# untitled.net
KiCad netlist of a schematic drawn in EAGLE
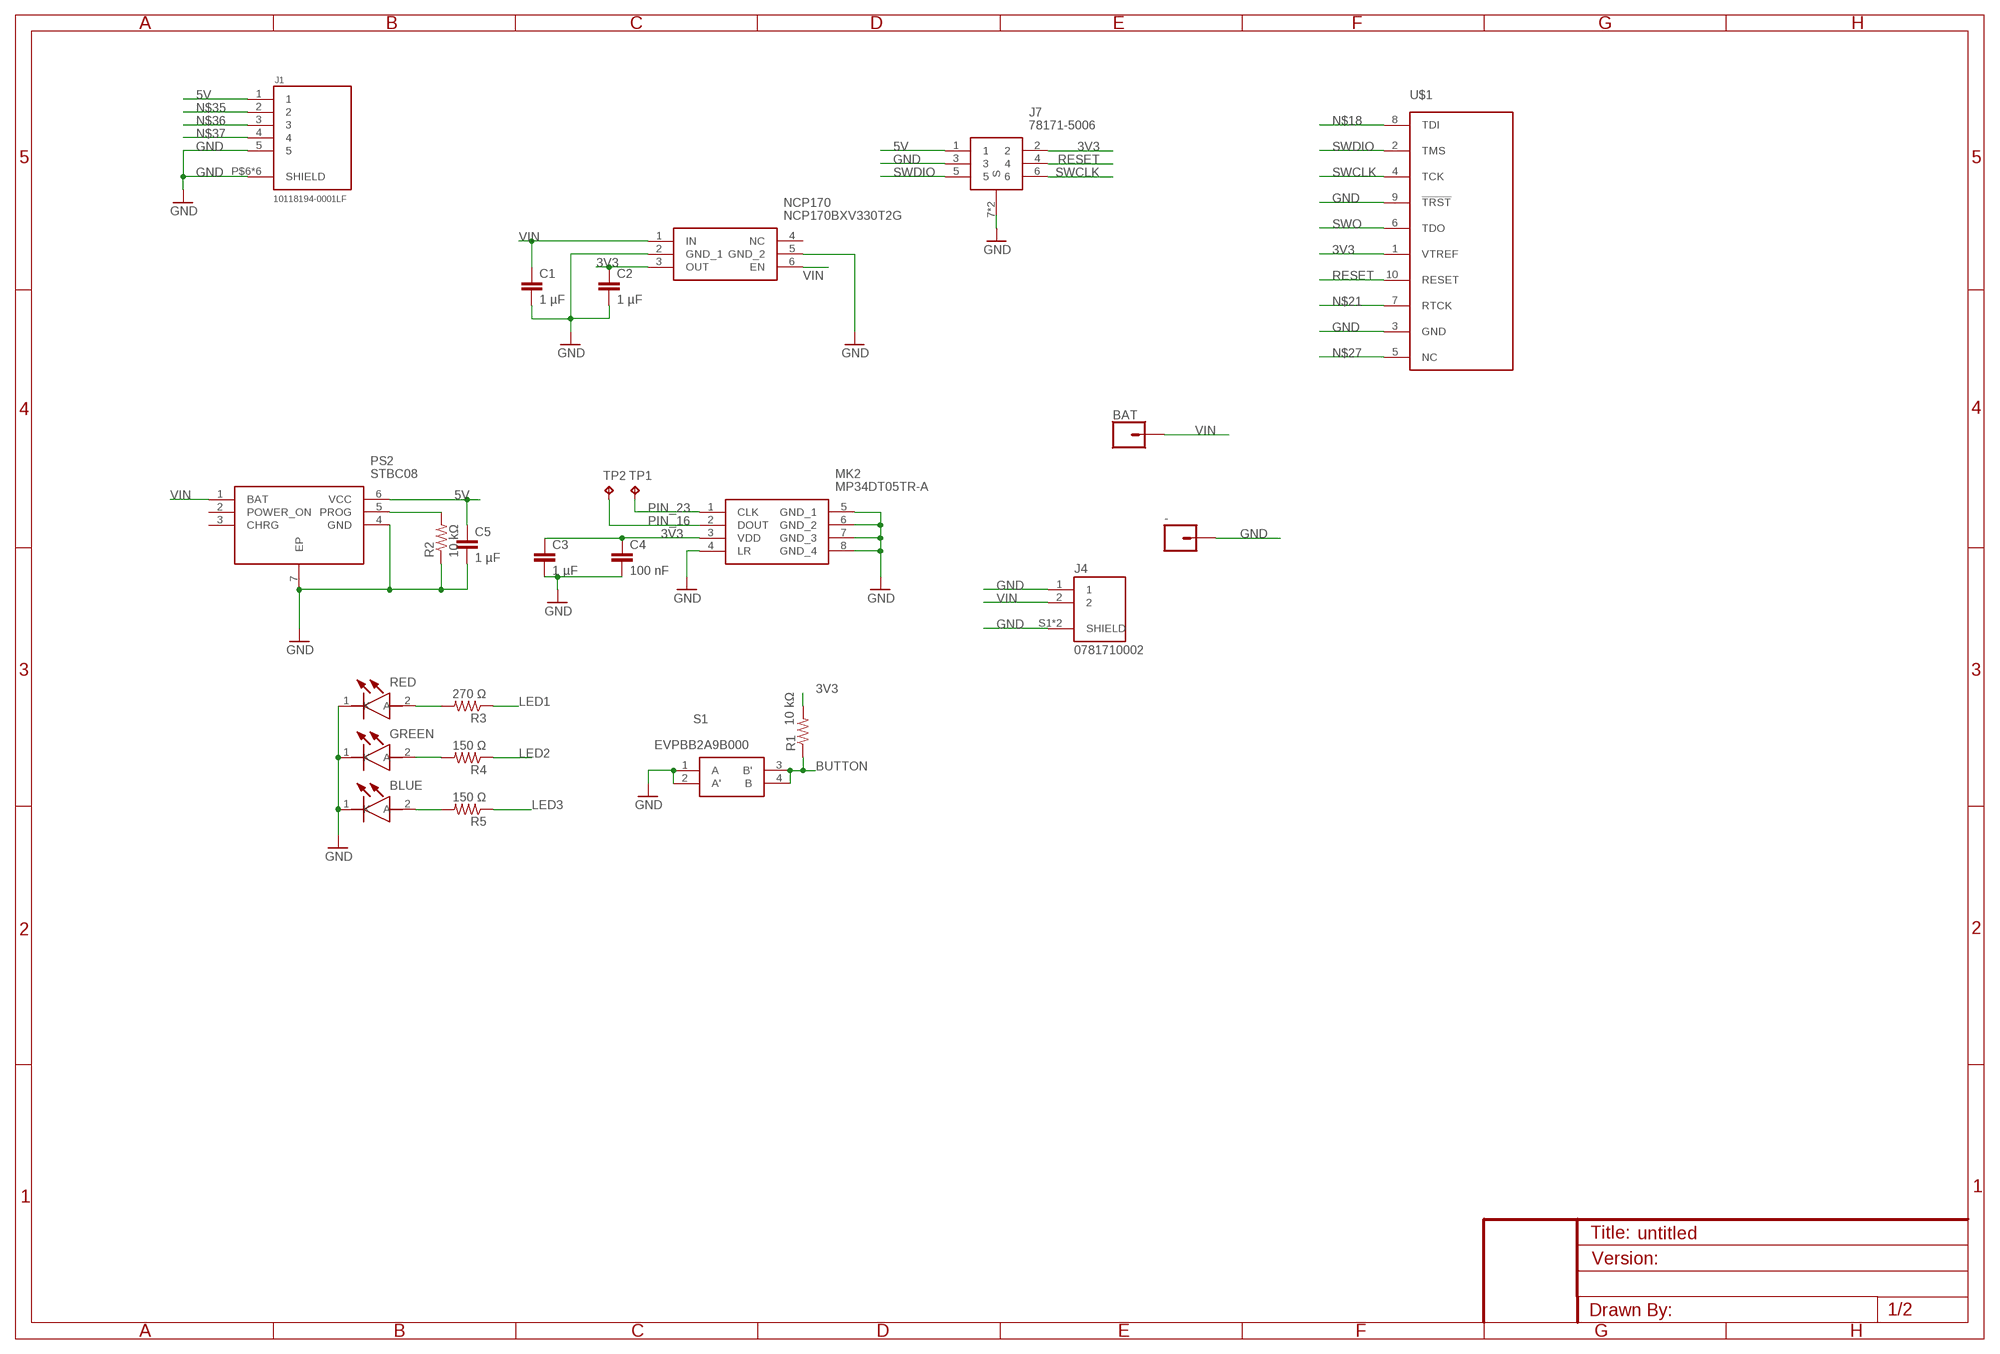
[diagram p0: schematic, sheet 1]
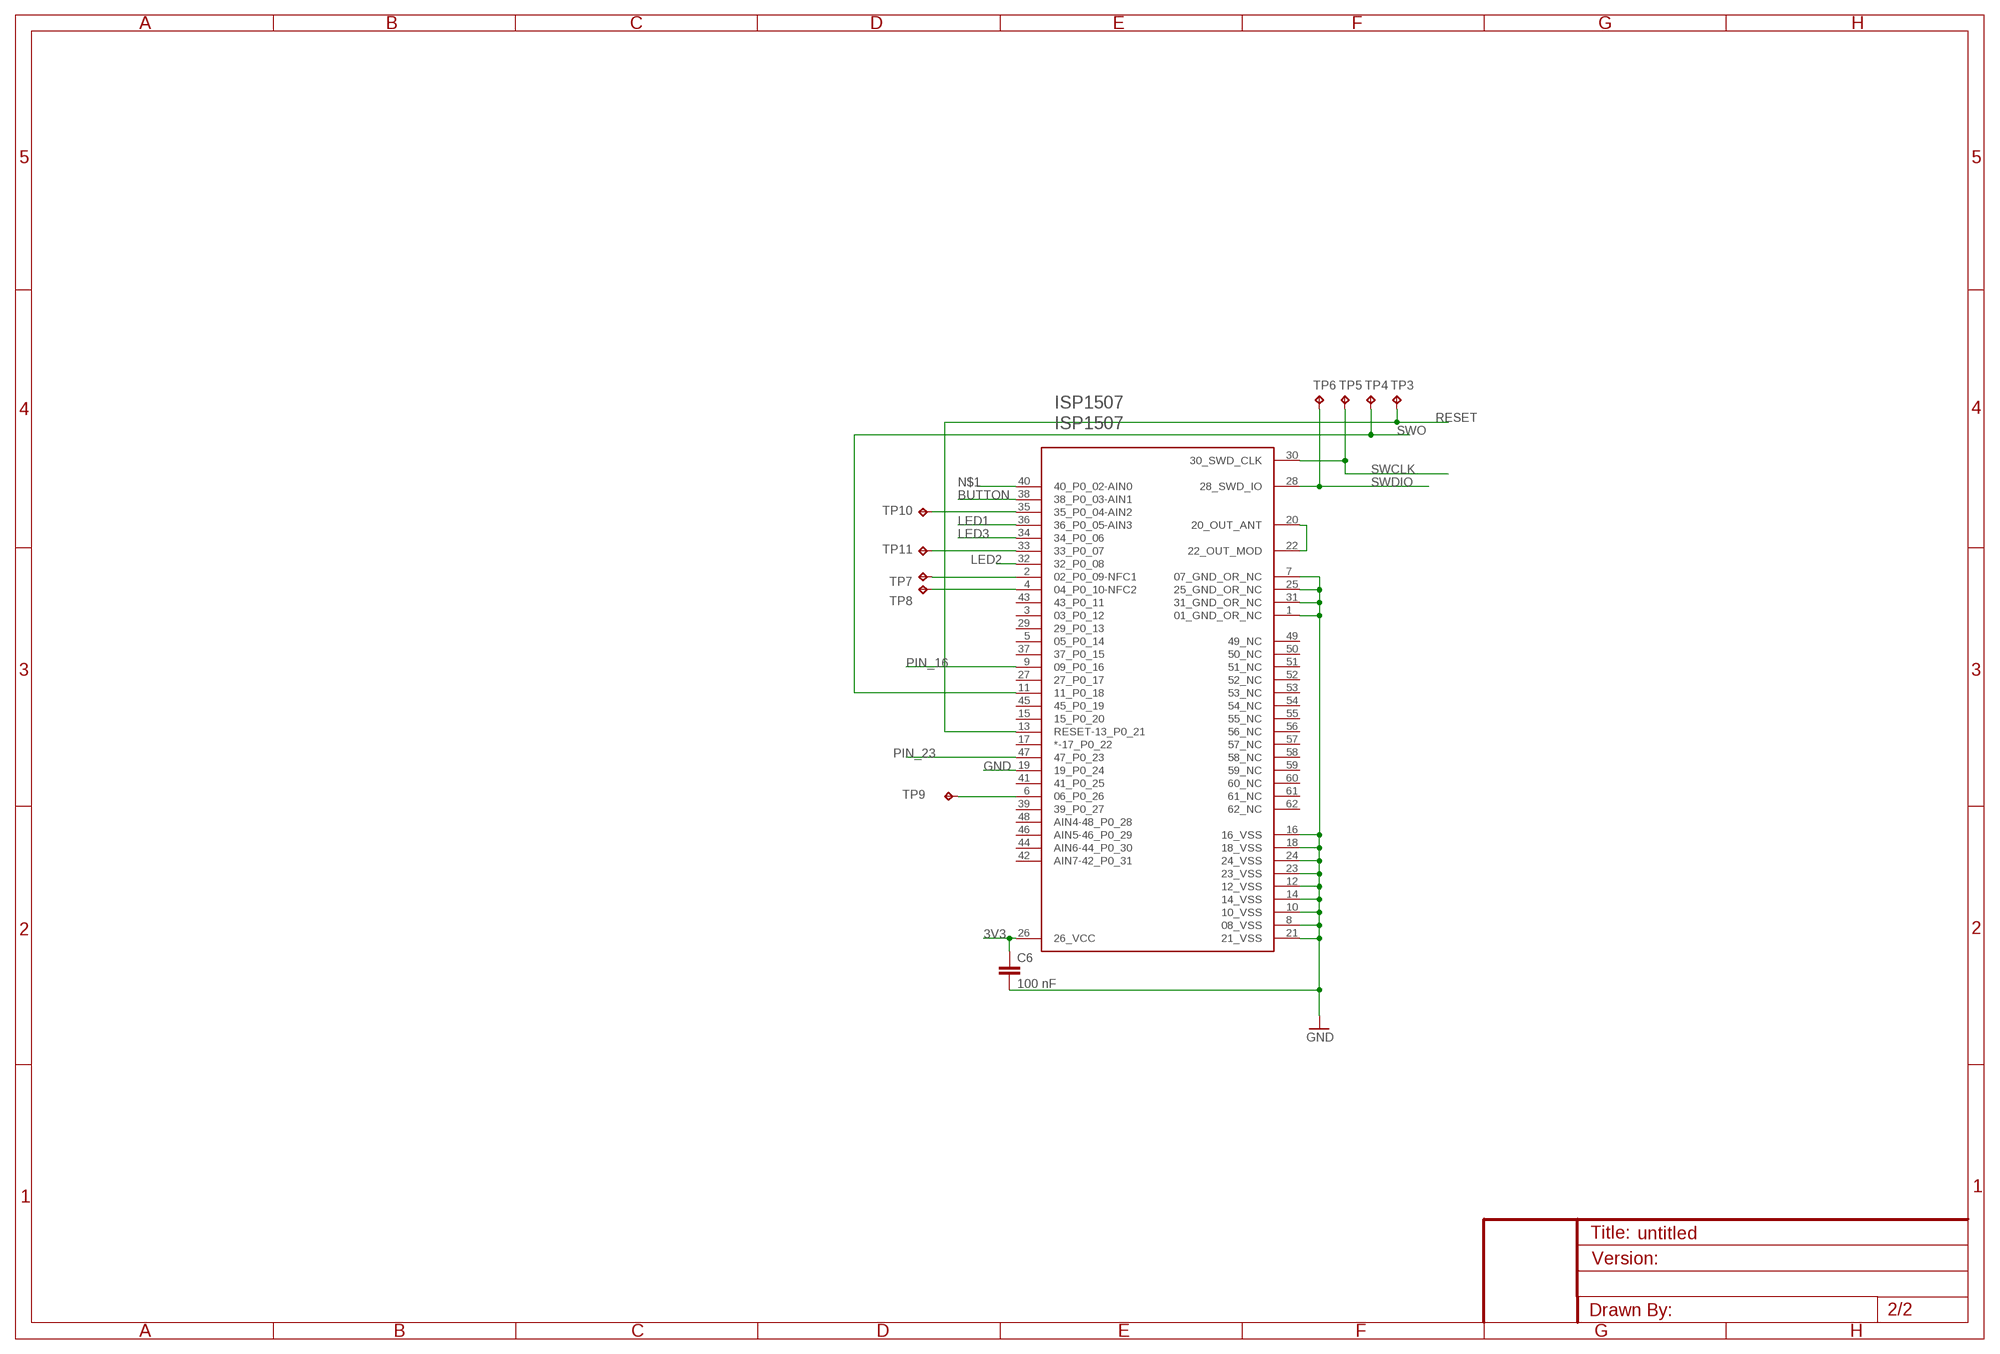
[diagram p1: schematic, sheet 2]

(export (version "E")
  (design (tool "Eeschema 10.0.6"))
  (components
    (comp (ref "-")
      (value "CONN_01")
      (footprint "eagle-import:1X01")
      (libsource (lib "eagle-import") (part "CONN_01"))
    )
    (comp (ref "BAT")
      (value "CONN_01")
      (footprint "eagle-import:1X01")
      (libsource (lib "eagle-import") (part "CONN_01"))
    )
    (comp (ref "BLUE")
      (value "150040GS73220")
      (footprint "eagle-import:LEDC1005X50N")
      (libsource (lib "eagle-import") (part "150040GS73220"))
    )
    (comp (ref "C1")
      (value "1 µF")
      (footprint "eagle-import:SPARKFUN_0402-CAP")
      (libsource (lib "eagle-import") (part "SPARKFUN_CAP0402-CAP"))
    )
    (comp (ref "C2")
      (value "1 µF")
      (footprint "eagle-import:SPARKFUN_0402-CAP")
      (libsource (lib "eagle-import") (part "SPARKFUN_CAP0402-CAP"))
    )
    (comp (ref "C3")
      (value "1 µF")
      (footprint "eagle-import:SPARKFUN_0402-CAP")
      (libsource (lib "eagle-import") (part "SPARKFUN_CAP0402-CAP"))
    )
    (comp (ref "C4")
      (value "100 nF")
      (footprint "eagle-import:SPARKFUN_0402-CAP")
      (libsource (lib "eagle-import") (part "SPARKFUN_CAP0402-CAP"))
    )
    (comp (ref "C5")
      (value "1 µF")
      (footprint "eagle-import:SPARKFUN_0402-CAP")
      (libsource (lib "eagle-import") (part "SPARKFUN_CAP0402-CAP"))
    )
    (comp (ref "GREEN")
      (value "150040GS73220")
      (footprint "eagle-import:LEDC1005X50N")
      (libsource (lib "eagle-import") (part "150040GS73220"))
    )
    (comp (ref "J1")
      (value "10118194-0001LF")
      (footprint "eagle-import:AMPHENOL_10118194-0001LF")
      (libsource (lib "eagle-import") (part "10118194-0001LF"))
    )
    (comp (ref "J4")
      (value "0781710002")
      (footprint "eagle-import:MOLEX_0781710002")
      (fields (field (name "MF") "Molex"))
      (libsource (lib "eagle-import") (part "0781710002"))
    )
    (comp (ref "J7")
      (value "78171-5006")
      (footprint "eagle-import:78171-5006")
      (fields (field (name "MOUSER_PART_NUMBER") "538-78171-5006") (field (name "RS_PART_NUMBER") "8967484"))
      (libsource (lib "eagle-import") (part "78171-5006"))
    )
    (comp (ref "MK2")
      (value "MP34DT05TR-A")
      (footprint "eagle-import:MP34DT05TRA")
      (fields (field (name "MOUSER_PART_NUMBER") "511-MP34DT05TR-A"))
      (libsource (lib "eagle-import") (part "MP34DT05TR-A"))
    )
    (comp (ref "NCP170")
      (value "NCP170BXV330T2G")
      (footprint "eagle-import:SOTFL50P160X60-6N")
      (fields (field (name "MOUSER_PART_NUMBER") "863-NCP170BXV330T2G"))
      (libsource (lib "eagle-import") (part "NCP170BXV330T2G"))
    )
    (comp (ref "PS2")
      (value "STBC08")
      (footprint "eagle-import:SON95P300X300X100-7N")
      (fields (field (name "ARROW_PART_NUMBER") "STBC08PMR") (field (name "RS_PART_NUMBER") "1655533"))
      (libsource (lib "eagle-import") (part "STBC08PMR"))
    )
    (comp (ref "R1")
      (value "10 kΩ")
      (footprint "eagle-import:SPARKFUN_0402-RES")
      (libsource (lib "eagle-import") (part "SPARKFUN_RESISTOR0402-RES"))
    )
    (comp (ref "R2")
      (value "10 kΩ")
      (footprint "eagle-import:SPARKFUN_0402-RES")
      (libsource (lib "eagle-import") (part "SPARKFUN_RESISTOR0402-RES"))
    )
    (comp (ref "R3")
      (value "270 Ω")
      (footprint "eagle-import:SPARKFUN_0402-RES")
      (libsource (lib "eagle-import") (part "SPARKFUN_RESISTOR0402-RES"))
    )
    (comp (ref "R4")
      (value "150 Ω")
      (footprint "eagle-import:SPARKFUN_0402-RES")
      (libsource (lib "eagle-import") (part "SPARKFUN_RESISTOR0402-RES"))
    )
    (comp (ref "R5")
      (value "150 Ω")
      (footprint "eagle-import:SPARKFUN_0402-RES")
      (libsource (lib "eagle-import") (part "SPARKFUN_RESISTOR0402-RES"))
    )
    (comp (ref "RED")
      (value "150040GS73220")
      (footprint "eagle-import:LEDC1005X50N")
      (libsource (lib "eagle-import") (part "150040GS73220"))
    )
    (comp (ref "S1")
      (value "EVPBB2A9B000")
      (footprint "eagle-import:EVPBB2A9B000")
      (fields (field (name "RS_PART_NUMBER") "1250187P"))
      (libsource (lib "eagle-import") (part "EVPBB2A9B000"))
    )
    (comp (ref "TP1")
      (value "TPTP06R")
      (footprint "eagle-import:TP06R")
      (libsource (lib "eagle-import") (part "TPTP06R"))
    )
    (comp (ref "TP2")
      (value "TPTP06R")
      (footprint "eagle-import:TP06R")
      (libsource (lib "eagle-import") (part "TPTP06R"))
    )
    (comp (ref "U$1")
      (value "TC2050-NL-MCP-NL")
      (footprint "eagle-import:TC2030-MCP-NL")
      (libsource (lib "eagle-import") (part "TC2050-NL-MCP-NL"))
    )
    (comp (ref "C6")
      (value "100 nF")
      (footprint "eagle-import:SPARKFUN_0402-CAP")
      (libsource (lib "eagle-import") (part "SPARKFUN_CAP0402-CAP"))
    )
    (comp (ref "ISP1507")
      (value "ISP1507")
      (footprint "eagle-import:ISP1507")
      (libsource (lib "eagle-import") (part "ISP1507"))
    )
    (comp (ref "TP3")
      (value "TPTP06R")
      (footprint "eagle-import:TP06R")
      (libsource (lib "eagle-import") (part "TPTP06R"))
    )
    (comp (ref "TP4")
      (value "TPTP06R")
      (footprint "eagle-import:TP06R")
      (libsource (lib "eagle-import") (part "TPTP06R"))
    )
    (comp (ref "TP5")
      (value "TPTP06R")
      (footprint "eagle-import:TP06R")
      (libsource (lib "eagle-import") (part "TPTP06R"))
    )
    (comp (ref "TP6")
      (value "TPTP06R")
      (footprint "eagle-import:TP06R")
      (libsource (lib "eagle-import") (part "TPTP06R"))
    )
    (comp (ref "TP7")
      (value "TPTP06R")
      (footprint "eagle-import:TP06R")
      (libsource (lib "eagle-import") (part "TPTP06R"))
    )
    (comp (ref "TP8")
      (value "TPTP06R")
      (footprint "eagle-import:TP06R")
      (libsource (lib "eagle-import") (part "TPTP06R"))
    )
    (comp (ref "TP9")
      (value "TPTP06R")
      (footprint "eagle-import:TP06R")
      (libsource (lib "eagle-import") (part "TPTP06R"))
    )
    (comp (ref "TP10")
      (value "TPTP06R")
      (footprint "eagle-import:TP06R")
      (libsource (lib "eagle-import") (part "TPTP06R"))
    )
    (comp (ref "TP11")
      (value "TPTP06R")
      (footprint "eagle-import:TP06R")
      (libsource (lib "eagle-import") (part "TPTP06R"))
    )
  )
  (nets
    (net (code "1") (name "3V3") (class "Default")
      (node (ref "C2") (pin "1") (pinfunction "1_1") (pintype "passive"))
      (node (ref "C3") (pin "1") (pinfunction "1_1") (pintype "passive"))
      (node (ref "C4") (pin "1") (pinfunction "1_1") (pintype "passive"))
      (node (ref "C6") (pin "1") (pinfunction "1_1") (pintype "passive"))
      (node (ref "ISP1507") (pin "26") (pinfunction "26_VCC_26") (pintype "power_in"))
      (node (ref "J7") (pin "2") (pinfunction "2_2") (pintype "bidirectional"))
      (node (ref "MK2") (pin "3") (pinfunction "VDD_3") (pintype "bidirectional"))
      (node (ref "NCP170") (pin "3") (pinfunction "OUT_3") (pintype "bidirectional"))
      (node (ref "R1") (pin "2") (pinfunction "2_2") (pintype "passive"))
      (node (ref "U$1") (pin "1") (pinfunction "VTREF_1") (pintype "bidirectional"))
    )
    (net (code "2") (name "5V") (class "Default")
      (node (ref "C5") (pin "1") (pinfunction "1_1") (pintype "passive"))
      (node (ref "J1") (pin "1") (pinfunction "1_1") (pintype "passive"))
      (node (ref "J7") (pin "1") (pinfunction "1_1") (pintype "bidirectional"))
      (node (ref "PS2") (pin "6") (pinfunction "VCC_6") (pintype "power_in"))
    )
    (net (code "3") (name "BUTTON") (class "Default")
      (node (ref "ISP1507") (pin "38") (pinfunction "38_P0_03-AIN1_38") (pintype "bidirectional"))
      (node (ref "R1") (pin "1") (pinfunction "1_1") (pintype "passive"))
      (node (ref "S1") (pin "3") (pinfunction "B'_3") (pintype "bidirectional"))
      (node (ref "S1") (pin "4") (pinfunction "B_4") (pintype "bidirectional"))
    )
    (net (code "4") (name "GND") (class "Default")
      (node (ref "-") (pin "1") (pinfunction "1_1") (pintype "passive"))
      (node (ref "BLUE") (pin "1") (pinfunction "K_1") (pintype "bidirectional"))
      (node (ref "C1") (pin "2") (pinfunction "2_2") (pintype "passive"))
      (node (ref "C2") (pin "2") (pinfunction "2_2") (pintype "passive"))
      (node (ref "C3") (pin "2") (pinfunction "2_2") (pintype "passive"))
      (node (ref "C4") (pin "2") (pinfunction "2_2") (pintype "passive"))
      (node (ref "C5") (pin "2") (pinfunction "2_2") (pintype "passive"))
      (node (ref "C6") (pin "2") (pinfunction "2_2") (pintype "passive"))
      (node (ref "GREEN") (pin "1") (pinfunction "K_1") (pintype "bidirectional"))
      (node (ref "ISP1507") (pin "1") (pinfunction "01_GND_OR_NC_1") (pintype "power_in"))
      (node (ref "ISP1507") (pin "10") (pinfunction "10_VSS_10") (pintype "power_in"))
      (node (ref "ISP1507") (pin "12") (pinfunction "12_VSS_12") (pintype "power_in"))
      (node (ref "ISP1507") (pin "14") (pinfunction "14_VSS_14") (pintype "power_in"))
      (node (ref "ISP1507") (pin "16") (pinfunction "16_VSS_16") (pintype "power_in"))
      (node (ref "ISP1507") (pin "18") (pinfunction "18_VSS_18") (pintype "power_in"))
      (node (ref "ISP1507") (pin "19") (pinfunction "19_P0_24_19") (pintype "bidirectional"))
      (node (ref "ISP1507") (pin "21") (pinfunction "21_VSS_21") (pintype "power_in"))
      (node (ref "ISP1507") (pin "23") (pinfunction "23_VSS_23") (pintype "power_in"))
      (node (ref "ISP1507") (pin "24") (pinfunction "24_VSS_24") (pintype "power_in"))
      (node (ref "ISP1507") (pin "25") (pinfunction "25_GND_OR_NC_25") (pintype "power_in"))
      (node (ref "ISP1507") (pin "31") (pinfunction "31_GND_OR_NC_31") (pintype "power_in"))
      (node (ref "ISP1507") (pin "7") (pinfunction "07_GND_OR_NC_7") (pintype "power_in"))
      (node (ref "ISP1507") (pin "8") (pinfunction "08_VSS_8") (pintype "power_in"))
      (node (ref "J1") (pin "5") (pinfunction "5_5") (pintype "passive"))
      (node (ref "J1") (pin "P$10") (pinfunction "SHIELD_P$10") (pintype "passive"))
      (node (ref "J1") (pin "P$11") (pinfunction "SHIELD_P$11") (pintype "passive"))
      (node (ref "J1") (pin "P$6") (pinfunction "SHIELD_P$6") (pintype "passive"))
      (node (ref "J1") (pin "P$7") (pinfunction "SHIELD_P$7") (pintype "passive"))
      (node (ref "J1") (pin "P$8") (pinfunction "SHIELD_P$8") (pintype "passive"))
      (node (ref "J1") (pin "P$9") (pinfunction "SHIELD_P$9") (pintype "passive"))
      (node (ref "J4") (pin "1") (pinfunction "1_1") (pintype "passive"))
      (node (ref "J4") (pin "S1") (pinfunction "SHIELD_S1") (pintype "passive"))
      (node (ref "J4") (pin "S2") (pinfunction "SHIELD_S2") (pintype "passive"))
      (node (ref "J7") (pin "3") (pinfunction "3_3") (pintype "bidirectional"))
      (node (ref "J7") (pin "7") (pinfunction "S_7") (pintype "bidirectional"))
      (node (ref "J7") (pin "8") (pinfunction "S_8") (pintype "bidirectional"))
      (node (ref "MK2") (pin "4") (pinfunction "LR_4") (pintype "bidirectional"))
      (node (ref "MK2") (pin "5") (pinfunction "GND_1_5") (pintype "bidirectional"))
      (node (ref "MK2") (pin "6") (pinfunction "GND_2_6") (pintype "bidirectional"))
      (node (ref "MK2") (pin "7") (pinfunction "GND_3_7") (pintype "bidirectional"))
      (node (ref "MK2") (pin "8") (pinfunction "GND_4_8") (pintype "bidirectional"))
      (node (ref "NCP170") (pin "2") (pinfunction "GND_1_2") (pintype "bidirectional"))
      (node (ref "NCP170") (pin "5") (pinfunction "GND_2_5") (pintype "bidirectional"))
      (node (ref "PS2") (pin "4") (pinfunction "GND_4") (pintype "power_in"))
      (node (ref "PS2") (pin "7") (pinfunction "EP_7") (pintype "power_in"))
      (node (ref "R2") (pin "1") (pinfunction "1_1") (pintype "passive"))
      (node (ref "RED") (pin "1") (pinfunction "K_1") (pintype "bidirectional"))
      (node (ref "S1") (pin "1") (pinfunction "A_1") (pintype "bidirectional"))
      (node (ref "S1") (pin "2") (pinfunction "A'_2") (pintype "bidirectional"))
      (node (ref "U$1") (pin "3") (pinfunction "GND_3") (pintype "bidirectional"))
      (node (ref "U$1") (pin "9") (pinfunction "~{TRST}_9") (pintype "bidirectional"))
    )
    (net (code "5") (name "LED1") (class "Default")
      (node (ref "ISP1507") (pin "36") (pinfunction "36_P0_05-AIN3_36") (pintype "bidirectional"))
      (node (ref "R3") (pin "1") (pinfunction "1_1") (pintype "passive"))
    )
    (net (code "6") (name "LED2") (class "Default")
      (node (ref "ISP1507") (pin "32") (pinfunction "32_P0_08_32") (pintype "bidirectional"))
      (node (ref "R4") (pin "1") (pinfunction "1_1") (pintype "passive"))
    )
    (net (code "7") (name "LED3") (class "Default")
      (node (ref "ISP1507") (pin "34") (pinfunction "34_P0_06_34") (pintype "bidirectional"))
      (node (ref "R5") (pin "1") (pinfunction "1_1") (pintype "passive"))
    )
    (net (code "8") (name "N$1") (class "Default")
      (node (ref "ISP1507") (pin "40") (pinfunction "40_P0_02-AIN0_40") (pintype "bidirectional"))
    )
    (net (code "9") (name "N$18") (class "Default")
      (node (ref "U$1") (pin "8") (pinfunction "TDI_8") (pintype "bidirectional"))
    )
    (net (code "10") (name "N$21") (class "Default")
      (node (ref "U$1") (pin "7") (pinfunction "RTCK_7") (pintype "bidirectional"))
    )
    (net (code "11") (name "N$27") (class "Default")
      (node (ref "U$1") (pin "5") (pinfunction "NC_5") (pintype "bidirectional"))
    )
    (net (code "12") (name "N$35") (class "Default")
      (node (ref "J1") (pin "2") (pinfunction "2_2") (pintype "passive"))
    )
    (net (code "13") (name "N$36") (class "Default")
      (node (ref "J1") (pin "3") (pinfunction "3_3") (pintype "passive"))
    )
    (net (code "14") (name "N$37") (class "Default")
      (node (ref "J1") (pin "4") (pinfunction "4_4") (pintype "passive"))
    )
    (net (code "15") (name "Net-(BLUE-A)") (class "Default")
      (node (ref "BLUE") (pin "2") (pinfunction "A_2") (pintype "bidirectional"))
      (node (ref "R5") (pin "2") (pinfunction "2_2") (pintype "passive"))
    )
    (net (code "16") (name "Net-(GREEN-A)") (class "Default")
      (node (ref "GREEN") (pin "2") (pinfunction "A_2") (pintype "bidirectional"))
      (node (ref "R4") (pin "2") (pinfunction "2_2") (pintype "passive"))
    )
    (net (code "17") (name "Net-(ISP1507-02_P0_09-NFC1)") (class "Default")
      (node (ref "ISP1507") (pin "2") (pinfunction "02_P0_09-NFC1_2") (pintype "bidirectional"))
      (node (ref "TP7") (pin "TP") (pinfunction "TP_TP") (pintype "input"))
    )
    (net (code "18") (name "Net-(ISP1507-04_P0_10-NFC2)") (class "Default")
      (node (ref "ISP1507") (pin "4") (pinfunction "04_P0_10-NFC2_4") (pintype "bidirectional"))
      (node (ref "TP8") (pin "TP") (pinfunction "TP_TP") (pintype "input"))
    )
    (net (code "19") (name "Net-(ISP1507-06_P0_26)") (class "Default")
      (node (ref "ISP1507") (pin "6") (pinfunction "06_P0_26_6") (pintype "bidirectional"))
      (node (ref "TP9") (pin "TP") (pinfunction "TP_TP") (pintype "input"))
    )
    (net (code "20") (name "Net-(ISP1507-20_OUT_ANT)") (class "Default")
      (node (ref "ISP1507") (pin "20") (pinfunction "20_OUT_ANT_20") (pintype "bidirectional"))
      (node (ref "ISP1507") (pin "22") (pinfunction "22_OUT_MOD_22") (pintype "bidirectional"))
    )
    (net (code "21") (name "Net-(ISP1507-33_P0_07)") (class "Default")
      (node (ref "ISP1507") (pin "33") (pinfunction "33_P0_07_33") (pintype "bidirectional"))
      (node (ref "TP11") (pin "TP") (pinfunction "TP_TP") (pintype "input"))
    )
    (net (code "22") (name "Net-(ISP1507-35_P0_04-AIN2)") (class "Default")
      (node (ref "ISP1507") (pin "35") (pinfunction "35_P0_04-AIN2_35") (pintype "bidirectional"))
      (node (ref "TP10") (pin "TP") (pinfunction "TP_TP") (pintype "input"))
    )
    (net (code "23") (name "Net-(PS2-PROG)") (class "Default")
      (node (ref "PS2") (pin "5") (pinfunction "PROG_5") (pintype "input"))
      (node (ref "R2") (pin "2") (pinfunction "2_2") (pintype "passive"))
    )
    (net (code "24") (name "Net-(RED-A)") (class "Default")
      (node (ref "R3") (pin "2") (pinfunction "2_2") (pintype "passive"))
      (node (ref "RED") (pin "2") (pinfunction "A_2") (pintype "bidirectional"))
    )
    (net (code "25") (name "PIN_16") (class "Default")
      (node (ref "ISP1507") (pin "9") (pinfunction "09_P0_16_9") (pintype "bidirectional"))
      (node (ref "MK2") (pin "2") (pinfunction "DOUT_2") (pintype "bidirectional"))
      (node (ref "TP2") (pin "TP") (pinfunction "TP_TP") (pintype "input"))
    )
    (net (code "26") (name "PIN_23") (class "Default")
      (node (ref "ISP1507") (pin "47") (pinfunction "47_P0_23_47") (pintype "bidirectional"))
      (node (ref "MK2") (pin "1") (pinfunction "CLK_1") (pintype "bidirectional"))
      (node (ref "TP1") (pin "TP") (pinfunction "TP_TP") (pintype "input"))
    )
    (net (code "27") (name "RESET") (class "Default")
      (node (ref "ISP1507") (pin "13") (pinfunction "RESET-13_P0_21_13") (pintype "bidirectional"))
      (node (ref "J7") (pin "4") (pinfunction "4_4") (pintype "bidirectional"))
      (node (ref "TP3") (pin "TP") (pinfunction "TP_TP") (pintype "input"))
      (node (ref "U$1") (pin "10") (pinfunction "RESET_10") (pintype "bidirectional"))
    )
    (net (code "28") (name "SWCLK") (class "Default")
      (node (ref "ISP1507") (pin "30") (pinfunction "30_SWD_CLK_30") (pintype "bidirectional"))
      (node (ref "J7") (pin "6") (pinfunction "6_6") (pintype "bidirectional"))
      (node (ref "TP5") (pin "TP") (pinfunction "TP_TP") (pintype "input"))
      (node (ref "U$1") (pin "4") (pinfunction "TCK_4") (pintype "bidirectional"))
    )
    (net (code "29") (name "SWDIO") (class "Default")
      (node (ref "ISP1507") (pin "28") (pinfunction "28_SWD_IO_28") (pintype "bidirectional"))
      (node (ref "J7") (pin "5") (pinfunction "5_5") (pintype "bidirectional"))
      (node (ref "TP6") (pin "TP") (pinfunction "TP_TP") (pintype "input"))
      (node (ref "U$1") (pin "2") (pinfunction "TMS_2") (pintype "bidirectional"))
    )
    (net (code "30") (name "SWO") (class "Default")
      (node (ref "ISP1507") (pin "11") (pinfunction "11_P0_18_11") (pintype "bidirectional"))
      (node (ref "TP4") (pin "TP") (pinfunction "TP_TP") (pintype "input"))
      (node (ref "U$1") (pin "6") (pinfunction "TDO_6") (pintype "bidirectional"))
    )
    (net (code "31") (name "VIN") (class "Default")
      (node (ref "BAT") (pin "1") (pinfunction "1_1") (pintype "passive"))
      (node (ref "C1") (pin "1") (pinfunction "1_1") (pintype "passive"))
      (node (ref "J4") (pin "2") (pinfunction "2_2") (pintype "passive"))
      (node (ref "NCP170") (pin "1") (pinfunction "IN_1") (pintype "bidirectional"))
      (node (ref "NCP170") (pin "6") (pinfunction "EN_6") (pintype "bidirectional"))
      (node (ref "PS2") (pin "1") (pinfunction "BAT_1") (pintype "output"))
    )
    (net (code "32") (name "unconnected-(ISP1507-*-17_P0_22-Pad17)") (class "Default")
      (node (ref "ISP1507") (pin "17") (pinfunction "*-17_P0_22_17") (pintype "bidirectional"))
    )
    (net (code "33") (name "unconnected-(ISP1507-03_P0_12-Pad3)") (class "Default")
      (node (ref "ISP1507") (pin "3") (pinfunction "03_P0_12_3") (pintype "bidirectional"))
    )
    (net (code "34") (name "unconnected-(ISP1507-05_P0_14-Pad5)") (class "Default")
      (node (ref "ISP1507") (pin "5") (pinfunction "05_P0_14_5") (pintype "bidirectional"))
    )
    (net (code "35") (name "unconnected-(ISP1507-15_P0_20-Pad15)") (class "Default")
      (node (ref "ISP1507") (pin "15") (pinfunction "15_P0_20_15") (pintype "bidirectional"))
    )
    (net (code "36") (name "unconnected-(ISP1507-27_P0_17-Pad27)") (class "Default")
      (node (ref "ISP1507") (pin "27") (pinfunction "27_P0_17_27") (pintype "bidirectional"))
    )
    (net (code "37") (name "unconnected-(ISP1507-29_P0_13-Pad29)") (class "Default")
      (node (ref "ISP1507") (pin "29") (pinfunction "29_P0_13_29") (pintype "bidirectional"))
    )
    (net (code "38") (name "unconnected-(ISP1507-37_P0_15-Pad37)") (class "Default")
      (node (ref "ISP1507") (pin "37") (pinfunction "37_P0_15_37") (pintype "bidirectional"))
    )
    (net (code "39") (name "unconnected-(ISP1507-39_P0_27-Pad39)") (class "Default")
      (node (ref "ISP1507") (pin "39") (pinfunction "39_P0_27_39") (pintype "bidirectional"))
    )
    (net (code "40") (name "unconnected-(ISP1507-41_P0_25-Pad41)") (class "Default")
      (node (ref "ISP1507") (pin "41") (pinfunction "41_P0_25_41") (pintype "bidirectional"))
    )
    (net (code "41") (name "unconnected-(ISP1507-43_P0_11-Pad43)") (class "Default")
      (node (ref "ISP1507") (pin "43") (pinfunction "43_P0_11_43") (pintype "bidirectional"))
    )
    (net (code "42") (name "unconnected-(ISP1507-45_P0_19-Pad45)") (class "Default")
      (node (ref "ISP1507") (pin "45") (pinfunction "45_P0_19_45") (pintype "bidirectional"))
    )
    (net (code "43") (name "unconnected-(ISP1507-49_NC-Pad49)") (class "Default")
      (node (ref "ISP1507") (pin "49") (pinfunction "49_NC_49") (pintype "no_connect"))
    )
    (net (code "44") (name "unconnected-(ISP1507-50_NC-Pad50)") (class "Default")
      (node (ref "ISP1507") (pin "50") (pinfunction "50_NC_50") (pintype "no_connect"))
    )
    (net (code "45") (name "unconnected-(ISP1507-51_NC-Pad51)") (class "Default")
      (node (ref "ISP1507") (pin "51") (pinfunction "51_NC_51") (pintype "no_connect"))
    )
    (net (code "46") (name "unconnected-(ISP1507-52_NC-Pad52)") (class "Default")
      (node (ref "ISP1507") (pin "52") (pinfunction "52_NC_52") (pintype "no_connect"))
    )
    (net (code "47") (name "unconnected-(ISP1507-53_NC-Pad53)") (class "Default")
      (node (ref "ISP1507") (pin "53") (pinfunction "53_NC_53") (pintype "no_connect"))
    )
    (net (code "48") (name "unconnected-(ISP1507-54_NC-Pad54)") (class "Default")
      (node (ref "ISP1507") (pin "54") (pinfunction "54_NC_54") (pintype "no_connect"))
    )
    (net (code "49") (name "unconnected-(ISP1507-55_NC-Pad55)") (class "Default")
      (node (ref "ISP1507") (pin "55") (pinfunction "55_NC_55") (pintype "no_connect"))
    )
    (net (code "50") (name "unconnected-(ISP1507-56_NC-Pad56)") (class "Default")
      (node (ref "ISP1507") (pin "56") (pinfunction "56_NC_56") (pintype "no_connect"))
    )
    (net (code "51") (name "unconnected-(ISP1507-57_NC-Pad57)") (class "Default")
      (node (ref "ISP1507") (pin "57") (pinfunction "57_NC_57") (pintype "no_connect"))
    )
    (net (code "52") (name "unconnected-(ISP1507-58_NC-Pad58)") (class "Default")
      (node (ref "ISP1507") (pin "58") (pinfunction "58_NC_58") (pintype "no_connect"))
    )
    (net (code "53") (name "unconnected-(ISP1507-59_NC-Pad59)") (class "Default")
      (node (ref "ISP1507") (pin "59") (pinfunction "59_NC_59") (pintype "no_connect"))
    )
    (net (code "54") (name "unconnected-(ISP1507-60_NC-Pad60)") (class "Default")
      (node (ref "ISP1507") (pin "60") (pinfunction "60_NC_60") (pintype "no_connect"))
    )
    (net (code "55") (name "unconnected-(ISP1507-61_NC-Pad61)") (class "Default")
      (node (ref "ISP1507") (pin "61") (pinfunction "61_NC_61") (pintype "no_connect"))
    )
    (net (code "56") (name "unconnected-(ISP1507-62_NC-Pad62)") (class "Default")
      (node (ref "ISP1507") (pin "62") (pinfunction "62_NC_62") (pintype "no_connect"))
    )
    (net (code "57") (name "unconnected-(ISP1507-AIN4-48_P0_28-Pad48)") (class "Default")
      (node (ref "ISP1507") (pin "48") (pinfunction "AIN4-48_P0_28_48") (pintype "bidirectional"))
    )
    (net (code "58") (name "unconnected-(ISP1507-AIN5-46_P0_29-Pad46)") (class "Default")
      (node (ref "ISP1507") (pin "46") (pinfunction "AIN5-46_P0_29_46") (pintype "bidirectional"))
    )
    (net (code "59") (name "unconnected-(ISP1507-AIN6-44_P0_30-Pad44)") (class "Default")
      (node (ref "ISP1507") (pin "44") (pinfunction "AIN6-44_P0_30_44") (pintype "bidirectional"))
    )
    (net (code "60") (name "unconnected-(ISP1507-AIN7-42_P0_31-Pad42)") (class "Default")
      (node (ref "ISP1507") (pin "42") (pinfunction "AIN7-42_P0_31_42") (pintype "bidirectional"))
    )
    (net (code "61") (name "unconnected-(NCP170-NC-Pad4)") (class "Default")
      (node (ref "NCP170") (pin "4") (pinfunction "NC_4") (pintype "no_connect"))
    )
    (net (code "62") (name "unconnected-(PS2-CHRG-Pad3)") (class "Default")
      (node (ref "PS2") (pin "3") (pinfunction "CHRG_3") (pintype "output"))
    )
    (net (code "63") (name "unconnected-(PS2-POWER_ON-Pad2)") (class "Default")
      (node (ref "PS2") (pin "2") (pinfunction "POWER_ON_2") (pintype "bidirectional"))
    )
  )
)
